# RS232_-_USB.net
KiCad netlist of a schematic drawn in Altium Designer
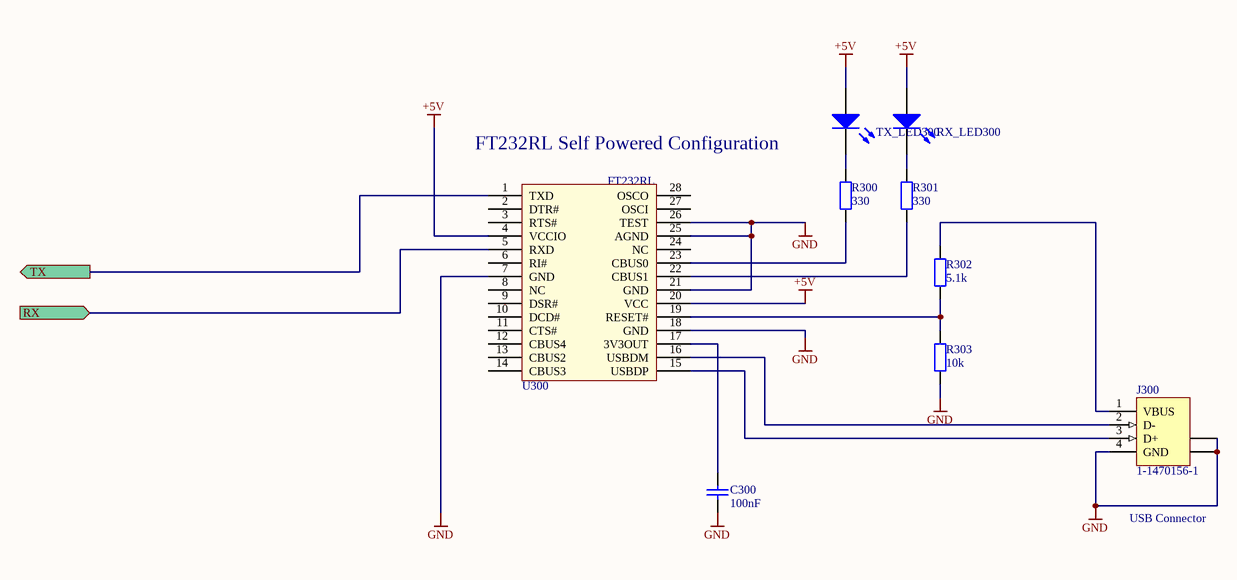
[diagram p0: RS232 - USB.SchDoc]

(export (version "E")
  (design (tool "Eeschema 10.0.6"))
  (components
    (comp (ref "C300")
      (value "100nF")
      (footprint "3216[1206]")
      (fields (field (name "Comment") "Cap"))
      (libsource (lib "Capacitors") (part "Cap"))
    )
    (comp (ref "J300")
      (value "1-1470156-1")
      (footprint "USB2.5-2H4D")
      (description "USB 1.1, Right Angle, Thru-Hole, B Type, Receptacle, 4 Position, White")
      (fields (field (name "PUBLISHER") "Altium Limited"))
      (libsource (lib "AMP Serial Bus USB") (part "1-1470156-1"))
    )
    (comp (ref "R300")
      (value "330")
      (footprint "3216[1206]")
      (fields (field (name "Comment") "Resistor"))
      (libsource (lib "Resistor") (part "RES1"))
    )
    (comp (ref "R301")
      (value "330")
      (footprint "3216[1206]")
      (fields (field (name "Comment") "Resistor"))
      (libsource (lib "Resistor") (part "RES1"))
    )
    (comp (ref "R302")
      (value "5.1k")
      (footprint "3216[1206]")
      (fields (field (name "Comment") "Resistor"))
      (libsource (lib "Resistor") (part "RES1"))
    )
    (comp (ref "R303")
      (value "10k")
      (footprint "3216[1206]")
      (fields (field (name "Comment") "Resistor"))
      (libsource (lib "Resistor") (part "RES1"))
    )
    (comp (ref "RX_LED300") (value "LED") (footprint "LED_1206") (libsource (lib "LED") (part "LED")))
    (comp (ref "TX_LED300") (value "LED") (footprint "LED_1206") (libsource (lib "LED") (part "LED")))
    (comp (ref "U300") (value "FT232RL") (footprint "SSOP28") (libsource (lib "COMM") (part "FT232RL")))
  )
  (nets
    (net (code "1") (name "+5V") (class "Default")
      (node (ref "RX_LED300") (pin "A") (pinfunction "A_A") (pintype "passive"))
      (node (ref "TX_LED300") (pin "A") (pinfunction "A_A") (pintype "passive"))
      (node (ref "U300") (pin "20") (pinfunction "VCC_20") (pintype "passive"))
      (node (ref "U300") (pin "4") (pinfunction "VCCIO_4") (pintype "passive"))
    )
    (net (code "2") (name "/RX") (class "Default")
      (node (ref "U300") (pin "5") (pinfunction "RXD_5") (pintype "passive"))
    )
    (net (code "3") (name "/TX") (class "Default")
      (node (ref "U300") (pin "1") (pinfunction "TXD_1") (pintype "passive"))
    )
    (net (code "4") (name "GND") (class "Default")
      (node (ref "C300") (pin "1") (pinfunction "1_1") (pintype "passive"))
      (node (ref "J300") (pin "4") (pinfunction "GND_4") (pintype "power_in"))
      (node (ref "J300") (pin "5") (pinfunction "SHLD_5") (pintype "passive"))
      (node (ref "J300") (pin "6") (pinfunction "SHLD_6") (pintype "passive"))
      (node (ref "R303") (pin "1") (pinfunction "1_1") (pintype "passive"))
      (node (ref "U300") (pin "18") (pinfunction "GND_18") (pintype "passive"))
      (node (ref "U300") (pin "21") (pinfunction "GND_21") (pintype "passive"))
      (node (ref "U300") (pin "25") (pinfunction "AGND_25") (pintype "passive"))
      (node (ref "U300") (pin "26") (pinfunction "TEST_26") (pintype "passive"))
      (node (ref "U300") (pin "7") (pinfunction "GND_7") (pintype "passive"))
    )
    (net (code "5") (name "Net-(J300-D+)") (class "Default")
      (node (ref "J300") (pin "3") (pinfunction "D+_3") (pintype "input"))
      (node (ref "U300") (pin "15") (pinfunction "USBDP_15") (pintype "passive"))
    )
    (net (code "6") (name "Net-(J300-D-)") (class "Default")
      (node (ref "J300") (pin "2") (pinfunction "D-_2") (pintype "input"))
      (node (ref "U300") (pin "16") (pinfunction "USBDM_16") (pintype "passive"))
    )
    (net (code "7") (name "Net-(J300-VBUS)") (class "Default")
      (node (ref "J300") (pin "1") (pinfunction "VBUS_1") (pintype "power_in"))
      (node (ref "R302") (pin "2") (pinfunction "2_2") (pintype "passive"))
    )
    (net (code "8") (name "Net-(R300-Pad2)") (class "Default")
      (node (ref "R300") (pin "2") (pinfunction "2_2") (pintype "passive"))
      (node (ref "TX_LED300") (pin "K") (pinfunction "K_K") (pintype "passive"))
    )
    (net (code "9") (name "Net-(R301-Pad2)") (class "Default")
      (node (ref "R301") (pin "2") (pinfunction "2_2") (pintype "passive"))
      (node (ref "RX_LED300") (pin "K") (pinfunction "K_K") (pintype "passive"))
    )
    (net (code "10") (name "Net-(U300-3V3OUT)") (class "Default")
      (node (ref "C300") (pin "2") (pinfunction "2_2") (pintype "passive"))
      (node (ref "U300") (pin "17") (pinfunction "3V3OUT_17") (pintype "passive"))
    )
    (net (code "11") (name "Net-(U300-CBUS0)") (class "Default")
      (node (ref "R300") (pin "1") (pinfunction "1_1") (pintype "passive"))
      (node (ref "U300") (pin "23") (pinfunction "CBUS0_23") (pintype "passive"))
    )
    (net (code "12") (name "Net-(U300-CBUS1)") (class "Default")
      (node (ref "R301") (pin "1") (pinfunction "1_1") (pintype "passive"))
      (node (ref "U300") (pin "22") (pinfunction "CBUS1_22") (pintype "passive"))
    )
    (net (code "13") (name "Net-(U300-RESET#)") (class "Default")
      (node (ref "R302") (pin "1") (pinfunction "1_1") (pintype "passive"))
      (node (ref "R303") (pin "2") (pinfunction "2_2") (pintype "passive"))
      (node (ref "U300") (pin "19") (pinfunction "RESET#_19") (pintype "passive"))
    )
    (net (code "14") (name "unconnected-(U300-CBUS2-Pad13)") (class "Default")
      (node (ref "U300") (pin "13") (pinfunction "CBUS2_13") (pintype "passive"))
    )
    (net (code "15") (name "unconnected-(U300-CBUS3-Pad14)") (class "Default")
      (node (ref "U300") (pin "14") (pinfunction "CBUS3_14") (pintype "passive"))
    )
    (net (code "16") (name "unconnected-(U300-CBUS4-Pad12)") (class "Default")
      (node (ref "U300") (pin "12") (pinfunction "CBUS4_12") (pintype "passive"))
    )
    (net (code "17") (name "unconnected-(U300-CTS#-Pad11)") (class "Default")
      (node (ref "U300") (pin "11") (pinfunction "CTS#_11") (pintype "passive"))
    )
    (net (code "18") (name "unconnected-(U300-DCD#-Pad10)") (class "Default")
      (node (ref "U300") (pin "10") (pinfunction "DCD#_10") (pintype "passive"))
    )
    (net (code "19") (name "unconnected-(U300-DSR#-Pad9)") (class "Default")
      (node (ref "U300") (pin "9") (pinfunction "DSR#_9") (pintype "passive"))
    )
    (net (code "20") (name "unconnected-(U300-DTR#-Pad2)") (class "Default")
      (node (ref "U300") (pin "2") (pinfunction "DTR#_2") (pintype "passive"))
    )
    (net (code "21") (name "unconnected-(U300-NC-Pad8)") (class "Default")
      (node (ref "U300") (pin "8") (pinfunction "NC_8") (pintype "passive"))
    )
    (net (code "22") (name "unconnected-(U300-NC-Pad24)") (class "Default")
      (node (ref "U300") (pin "24") (pinfunction "NC_24") (pintype "passive"))
    )
    (net (code "23") (name "unconnected-(U300-OSCI-Pad27)") (class "Default")
      (node (ref "U300") (pin "27") (pinfunction "OSCI_27") (pintype "passive"))
    )
    (net (code "24") (name "unconnected-(U300-OSCO-Pad28)") (class "Default")
      (node (ref "U300") (pin "28") (pinfunction "OSCO_28") (pintype "passive"))
    )
    (net (code "25") (name "unconnected-(U300-RI#-Pad6)") (class "Default")
      (node (ref "U300") (pin "6") (pinfunction "RI#_6") (pintype "passive"))
    )
    (net (code "26") (name "unconnected-(U300-RTS#-Pad3)") (class "Default")
      (node (ref "U300") (pin "3") (pinfunction "RTS#_3") (pintype "passive"))
    )
  )
)
